# esperto_v1.net
KiCad netlist of a schematic drawn in EAGLE
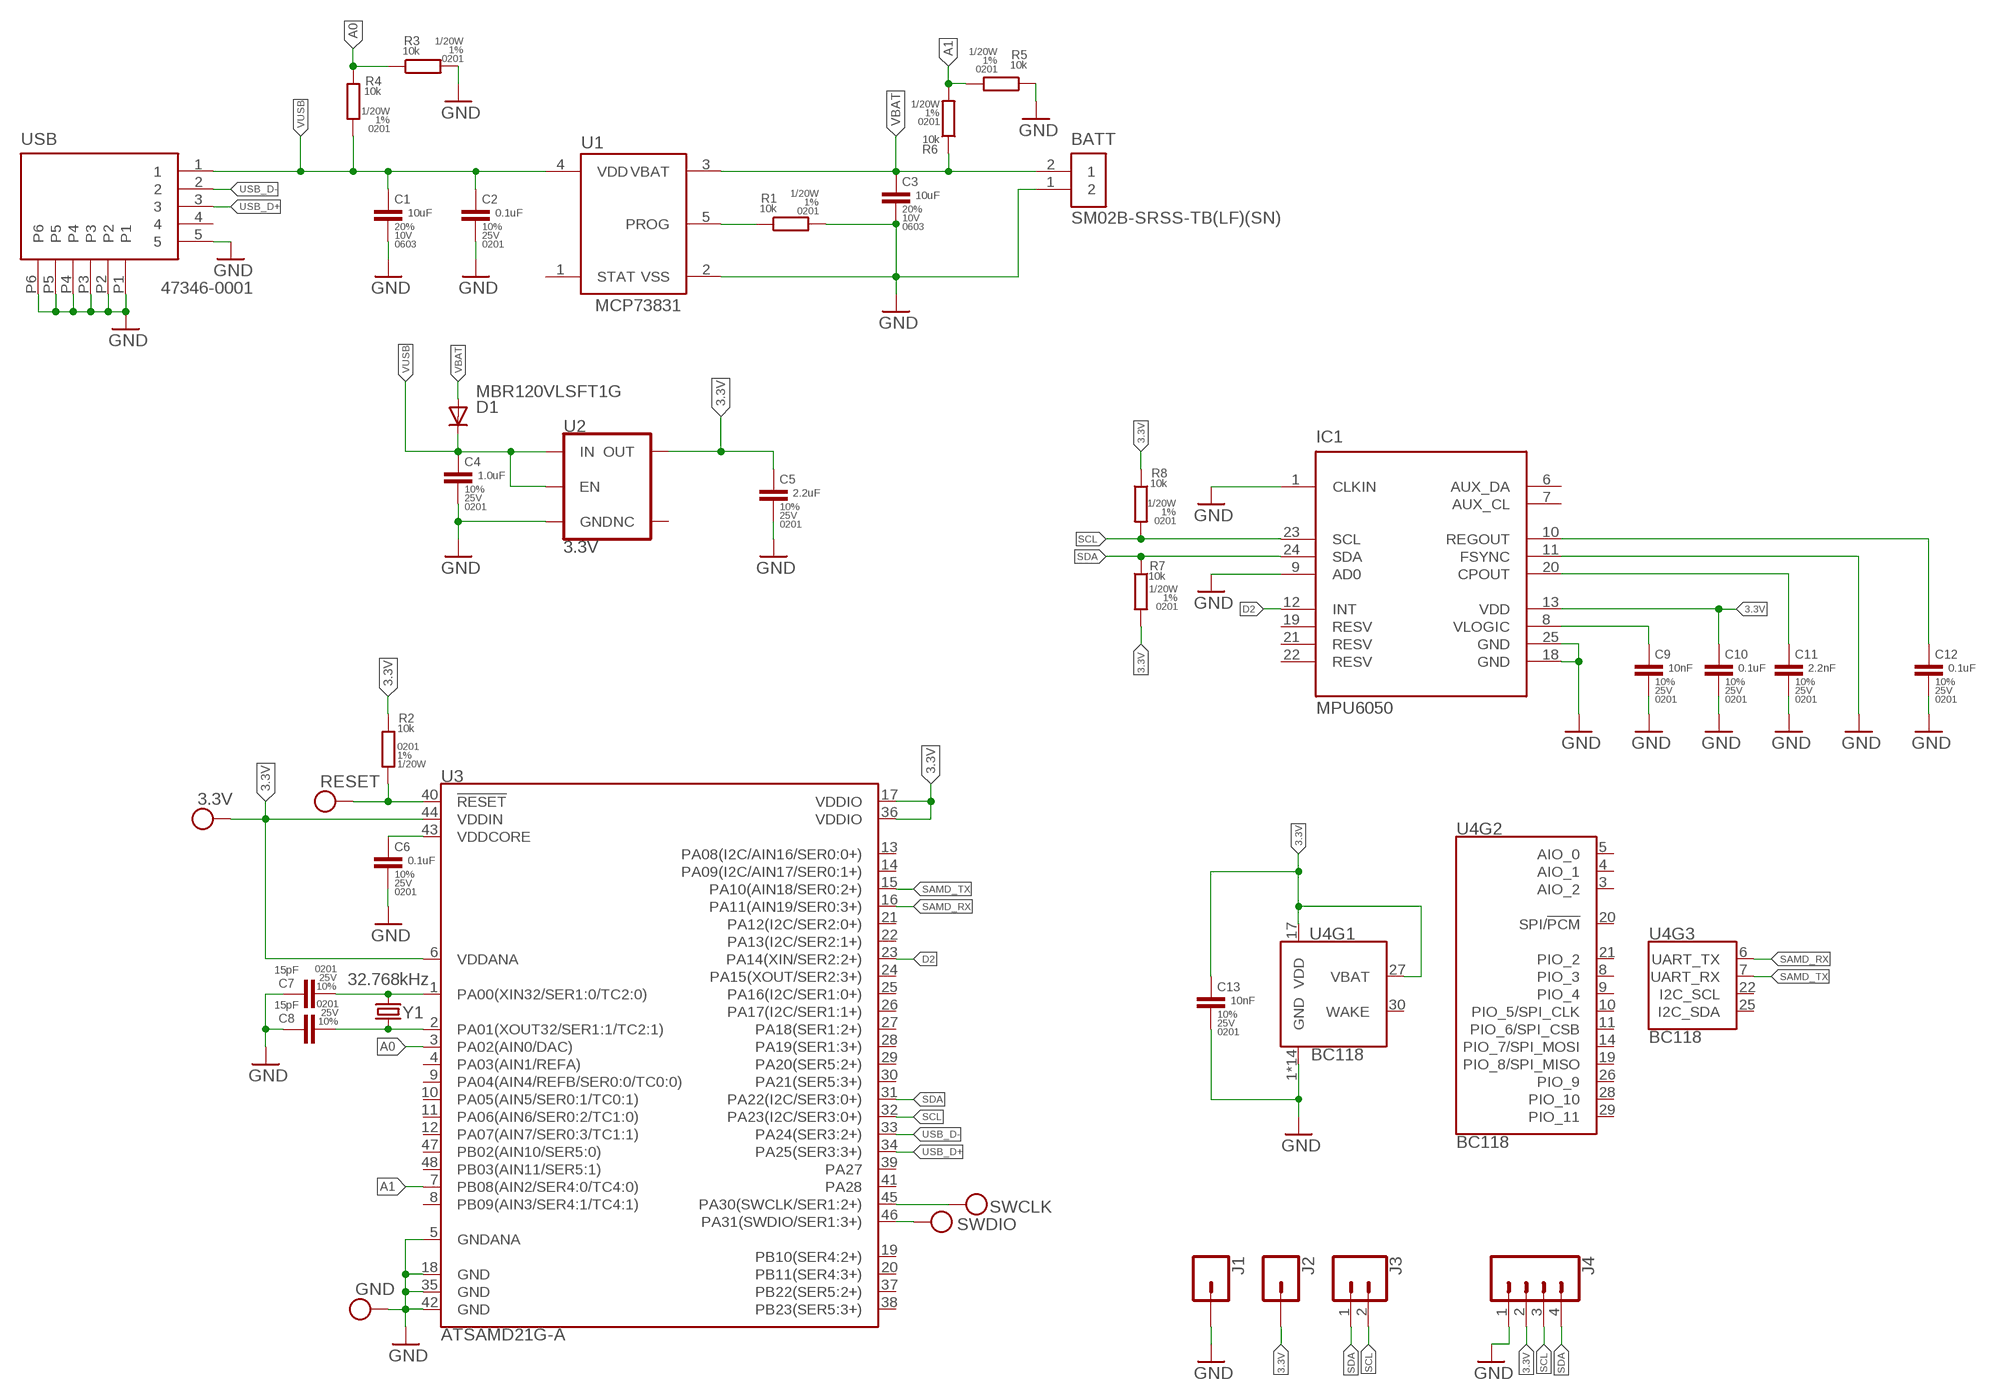
[diagram p0: schematic, sheet 1]

(export (version "E")
  (design (tool "Eeschema 10.0.6"))
  (components
    (comp (ref "3.3V")
      (value "PIN_1X.05\"1")
      (footprint "eagle-import:1X.05_")
      (libsource (lib "eagle-import") (part "PIN_1X.05{dblquote}1"))
    )
    (comp (ref "BATT")
      (value "SM02B-SRSS-TB(LF)(SN)")
      (footprint "eagle-import:JST_SH_2X1")
      (fields (field (name "PARTNO") "AS-ITM-00231"))
      (libsource (lib "eagle-import") (part "AS-ITM-00231"))
    )
    (comp (ref "C1")
      (value "10uF")
      (footprint "eagle-import:C0603_MURATA_GRM18")
      (fields (field (name "TOLERANCE") "20%"))
      (libsource (lib "eagle-import") (part "C-EUC0603_MURATA_GRM18"))
    )
    (comp (ref "C2")
      (value "0.1uF")
      (footprint "eagle-import:C0201_MURATA_GRM03")
      (fields (field (name "TOLERANCE") "10%"))
      (libsource (lib "eagle-import") (part "C-EUC0201_MURATA_GRM03"))
    )
    (comp (ref "C3")
      (value "10uF")
      (footprint "eagle-import:C0603_MURATA_GRM18")
      (fields (field (name "TOLERANCE") "20%"))
      (libsource (lib "eagle-import") (part "C-EUC0603_MURATA_GRM18"))
    )
    (comp (ref "C4")
      (value "1.0uF")
      (footprint "eagle-import:C0201_MURATA_GRM03")
      (fields (field (name "TOLERANCE") "10%"))
      (libsource (lib "eagle-import") (part "C-EUC0201_MURATA_GRM03"))
    )
    (comp (ref "C5")
      (value "2.2uF")
      (footprint "eagle-import:C0201_MURATA_GRM03")
      (fields (field (name "TOLERANCE") "10%"))
      (libsource (lib "eagle-import") (part "C-EUC0201_MURATA_GRM03"))
    )
    (comp (ref "C6")
      (value "0.1uF")
      (footprint "eagle-import:C0201_MURATA_GRM03")
      (fields (field (name "TOLERANCE") "10%"))
      (libsource (lib "eagle-import") (part "C-EUC0201_MURATA_GRM03"))
    )
    (comp (ref "C7")
      (value "15pF")
      (footprint "eagle-import:C0201_MURATA_GRM03")
      (fields (field (name "RATING") "25V") (field (name "TOLERANCE") "10%") (field (name "PACKAGE") "0201"))
      (libsource (lib "eagle-import") (part "C-EUC0201_MURATA_GRM03"))
    )
    (comp (ref "C8")
      (value "15pF")
      (footprint "eagle-import:C0201_MURATA_GRM03")
      (fields (field (name "RATING") "25V") (field (name "TOLERANCE") "10%") (field (name "PACKAGE") "0201"))
      (libsource (lib "eagle-import") (part "C-EUC0201_MURATA_GRM03"))
    )
    (comp (ref "C9")
      (value "10nF")
      (footprint "eagle-import:C0201_MURATA_GRM03")
      (fields (field (name "TOLERANCE") "10%"))
      (libsource (lib "eagle-import") (part "C-EUC0201_MURATA_GRM03"))
    )
    (comp (ref "C10")
      (value "0.1uF")
      (footprint "eagle-import:C0201_MURATA_GRM03")
      (fields (field (name "TOLERANCE") "10%"))
      (libsource (lib "eagle-import") (part "C-EUC0201_MURATA_GRM03"))
    )
    (comp (ref "C11")
      (value "2.2nF")
      (footprint "eagle-import:C0201_MURATA_GRM03")
      (fields (field (name "TOLERANCE") "10%"))
      (libsource (lib "eagle-import") (part "C-EUC0201_MURATA_GRM03"))
    )
    (comp (ref "C12")
      (value "0.1uF")
      (footprint "eagle-import:C0201_MURATA_GRM03")
      (fields (field (name "TOLERANCE") "10%"))
      (libsource (lib "eagle-import") (part "C-EUC0201_MURATA_GRM03"))
    )
    (comp (ref "C13")
      (value "10nF")
      (footprint "eagle-import:C0201_MURATA_GRM03")
      (fields (field (name "TOLERANCE") "10%"))
      (libsource (lib "eagle-import") (part "C-EUC0201_MURATA_GRM03"))
    )
    (comp (ref "D1")
      (value "MBR120VLSFT1G")
      (footprint "eagle-import:SOD-123FL")
      (fields (field (name "PARTNO") "AS-ITM-00111"))
      (libsource (lib "eagle-import") (part "AS-ITM-00111"))
    )
    (comp (ref "GND")
      (value "PIN_1X.05\"1")
      (footprint "eagle-import:1X.05_")
      (libsource (lib "eagle-import") (part "PIN_1X.05{dblquote}1"))
    )
    (comp (ref "IC1")
      (value "MPU6050")
      (footprint "eagle-import:QFN50P400X400X95-25T265X275N")
      (libsource (lib "eagle-import") (part "MPU6050"))
    )
    (comp (ref "J1")
      (value "CONN_01")
      (footprint "eagle-import:1X01")
      (libsource (lib "eagle-import") (part "CONN_01"))
    )
    (comp (ref "J2")
      (value "CONN_01")
      (footprint "eagle-import:1X01")
      (libsource (lib "eagle-import") (part "CONN_01"))
    )
    (comp (ref "J3")
      (value "CONN_02")
      (footprint "eagle-import:1X02")
      (libsource (lib "eagle-import") (part "CONN_02"))
    )
    (comp (ref "J4")
      (value "CONN_04")
      (footprint "eagle-import:1X04")
      (libsource (lib "eagle-import") (part "CONN_04"))
    )
    (comp (ref "R1")
      (value "10k")
      (footprint "eagle-import:R0201_VISHAY_CRCW0201")
      (fields (field (name "TOLERANCE") "1%") (field (name "RATING") "1/20W") (field (name "PACKAGE") "0201"))
      (libsource (lib "eagle-import") (part "R-EU_R0201_VISHAY_CRCW0201"))
    )
    (comp (ref "R2")
      (value "10k")
      (footprint "eagle-import:R0201_VISHAY_CRCW0201")
      (fields (field (name "TOLERANCE") "1%"))
      (libsource (lib "eagle-import") (part "R-EU_R0201_VISHAY_CRCW0201"))
    )
    (comp (ref "R3")
      (value "10k")
      (footprint "eagle-import:R0201_VISHAY_CRCW0201")
      (fields (field (name "TOLERANCE") "1%") (field (name "RATING") "1/20W") (field (name "PACKAGE") "0201"))
      (libsource (lib "eagle-import") (part "R-EU_R0201_VISHAY_CRCW0201"))
    )
    (comp (ref "R4")
      (value "10k")
      (footprint "eagle-import:R0201_VISHAY_CRCW0201")
      (fields (field (name "TOLERANCE") "1%") (field (name "RATING") "1/20W") (field (name "PACKAGE") "0201"))
      (libsource (lib "eagle-import") (part "R-EU_R0201_VISHAY_CRCW0201"))
    )
    (comp (ref "R5")
      (value "10k")
      (footprint "eagle-import:R0201_VISHAY_CRCW0201")
      (fields (field (name "TOLERANCE") "1%") (field (name "RATING") "1/20W") (field (name "PACKAGE") "0201"))
      (libsource (lib "eagle-import") (part "R-EU_R0201_VISHAY_CRCW0201"))
    )
    (comp (ref "R6")
      (value "10k")
      (footprint "eagle-import:R0201_VISHAY_CRCW0201")
      (fields (field (name "TOLERANCE") "1%"))
      (libsource (lib "eagle-import") (part "R-EU_R0201_VISHAY_CRCW0201"))
    )
    (comp (ref "R7")
      (value "10k")
      (footprint "eagle-import:R0201_VISHAY_CRCW0201")
      (fields (field (name "TOLERANCE") "1%") (field (name "RATING") "1/20W") (field (name "PACKAGE") "0201"))
      (libsource (lib "eagle-import") (part "R-EU_R0201_VISHAY_CRCW0201"))
    )
    (comp (ref "R8")
      (value "10k")
      (footprint "eagle-import:R0201_VISHAY_CRCW0201")
      (fields (field (name "TOLERANCE") "1%") (field (name "RATING") "1/20W") (field (name "PACKAGE") "0201"))
      (libsource (lib "eagle-import") (part "R-EU_R0201_VISHAY_CRCW0201"))
    )
    (comp (ref "RESET")
      (value "PIN_1X.05\"1")
      (footprint "eagle-import:1X.05_")
      (libsource (lib "eagle-import") (part "PIN_1X.05{dblquote}1"))
    )
    (comp (ref "SWCLK")
      (value "PIN_1X.05\"1")
      (footprint "eagle-import:1X.05_")
      (libsource (lib "eagle-import") (part "PIN_1X.05{dblquote}1"))
    )
    (comp (ref "SWDIO")
      (value "PIN_1X.05\"1")
      (footprint "eagle-import:1X.05_")
      (libsource (lib "eagle-import") (part "PIN_1X.05{dblquote}1"))
    )
    (comp (ref "U1")
      (value "MCP73831")
      (footprint "eagle-import:SOT-23")
      (fields (field (name "PARTNO") "AS-ITM-00136"))
      (libsource (lib "eagle-import") (part "AS-ITM-00136"))
    )
    (comp (ref "U2")
      (value "3.3V")
      (footprint "eagle-import:SOT23-5")
      (libsource (lib "eagle-import") (part "V_REG_AP2112K-3.3V"))
    )
    (comp (ref "U3")
      (value "ATSAMD21G-A")
      (footprint "eagle-import:TQFP-48")
      (libsource (lib "eagle-import") (part "ATSAMD21G-A"))
    )
    (comp (ref "U4")
      (value "BC118")
      (footprint "eagle-import:BC118")
      (libsource (lib "eagle-import") (part "BC118"))
    )
    (comp (ref "USB")
      (value "47346-0001")
      (footprint "eagle-import:MICRO_USB")
      (fields (field (name "PARTNO") "AS-ITM-00021"))
      (libsource (lib "eagle-import") (part "AS-ITM-00021"))
    )
    (comp (ref "Y1")
      (value "32.768kHz")
      (footprint "eagle-import:CRYSTAL-SMD-3.2X1.5MM")
      (libsource (lib "eagle-import") (part "CRYSTAL-32.768KHZSMD-3.2X1.5"))
    )
  )
  (nets
    (net (code "1") (name "3.3V") (class "Default")
      (node (ref "3.3V") (pin "1") (pinfunction "1_1") (pintype "bidirectional"))
      (node (ref "C10") (pin "1") (pinfunction "1_1") (pintype "passive"))
      (node (ref "C13") (pin "1") (pinfunction "1_1") (pintype "passive"))
      (node (ref "C5") (pin "1") (pinfunction "1_1") (pintype "passive"))
      (node (ref "IC1") (pin "13") (pinfunction "VDD_13") (pintype "power_in"))
      (node (ref "J2") (pin "1") (pinfunction "1_1") (pintype "passive"))
      (node (ref "J4") (pin "2") (pinfunction "2_2") (pintype "passive"))
      (node (ref "R2") (pin "1") (pinfunction "1_1") (pintype "passive"))
      (node (ref "R7") (pin "2") (pinfunction "2_2") (pintype "passive"))
      (node (ref "R8") (pin "1") (pinfunction "1_1") (pintype "passive"))
      (node (ref "U2") (pin "5") (pinfunction "OUT_5") (pintype "passive"))
      (node (ref "U3") (pin "17") (pinfunction "VDDIO_17") (pintype "bidirectional"))
      (node (ref "U3") (pin "36") (pinfunction "VDDIO_36") (pintype "bidirectional"))
      (node (ref "U3") (pin "44") (pinfunction "VDDIN_44") (pintype "bidirectional"))
      (node (ref "U3") (pin "6") (pinfunction "VDDANA_6") (pintype "bidirectional"))
      (node (ref "U4") (pin "17") (pinfunction "VDD_17") (pintype "bidirectional"))
      (node (ref "U4") (pin "27") (pinfunction "VBAT_27") (pintype "bidirectional"))
    )
    (net (code "2") (name "A0") (class "Default")
      (node (ref "R3") (pin "1") (pinfunction "1_1") (pintype "passive"))
      (node (ref "R4") (pin "1") (pinfunction "1_1") (pintype "passive"))
      (node (ref "U3") (pin "3") (pinfunction "PA02(AIN0/DAC)_3") (pintype "bidirectional"))
    )
    (net (code "3") (name "A1") (class "Default")
      (node (ref "R5") (pin "2") (pinfunction "2_2") (pintype "passive"))
      (node (ref "R6") (pin "2") (pinfunction "2_2") (pintype "passive"))
      (node (ref "U3") (pin "7") (pinfunction "PB08(AIN2/SER4:0/TC4:0)_7") (pintype "bidirectional"))
    )
    (net (code "4") (name "D2") (class "Default")
      (node (ref "IC1") (pin "12") (pinfunction "INT_12") (pintype "open_collector"))
      (node (ref "U3") (pin "23") (pinfunction "PA14(XIN/SER2:2+)_23") (pintype "bidirectional"))
    )
    (net (code "5") (name "GND") (class "Default")
      (node (ref "BATT") (pin "1") (pinfunction "2_1") (pintype "bidirectional"))
      (node (ref "C1") (pin "2") (pinfunction "2_2") (pintype "passive"))
      (node (ref "C10") (pin "2") (pinfunction "2_2") (pintype "passive"))
      (node (ref "C11") (pin "2") (pinfunction "2_2") (pintype "passive"))
      (node (ref "C12") (pin "2") (pinfunction "2_2") (pintype "passive"))
      (node (ref "C13") (pin "2") (pinfunction "2_2") (pintype "passive"))
      (node (ref "C2") (pin "2") (pinfunction "2_2") (pintype "passive"))
      (node (ref "C3") (pin "2") (pinfunction "2_2") (pintype "passive"))
      (node (ref "C4") (pin "2") (pinfunction "2_2") (pintype "passive"))
      (node (ref "C5") (pin "2") (pinfunction "2_2") (pintype "passive"))
      (node (ref "C6") (pin "2") (pinfunction "2_2") (pintype "passive"))
      (node (ref "C7") (pin "1") (pinfunction "1_1") (pintype "passive"))
      (node (ref "C8") (pin "1") (pinfunction "1_1") (pintype "passive"))
      (node (ref "C9") (pin "2") (pinfunction "2_2") (pintype "passive"))
      (node (ref "GND") (pin "1") (pinfunction "1_1") (pintype "bidirectional"))
      (node (ref "IC1") (pin "1") (pinfunction "CLKIN_1") (pintype "input"))
      (node (ref "IC1") (pin "11") (pinfunction "FSYNC_11") (pintype "input"))
      (node (ref "IC1") (pin "18") (pinfunction "GND_18") (pintype "power_in"))
      (node (ref "IC1") (pin "25") (pinfunction "GND_25") (pintype "power_in"))
      (node (ref "IC1") (pin "9") (pinfunction "AD0_9") (pintype "input"))
      (node (ref "J1") (pin "1") (pinfunction "1_1") (pintype "passive"))
      (node (ref "J4") (pin "1") (pinfunction "1_1") (pintype "passive"))
      (node (ref "R1") (pin "2") (pinfunction "2_2") (pintype "passive"))
      (node (ref "R3") (pin "2") (pinfunction "2_2") (pintype "passive"))
      (node (ref "R5") (pin "1") (pinfunction "1_1") (pintype "passive"))
      (node (ref "U1") (pin "2") (pinfunction "VSS_2") (pintype "bidirectional"))
      (node (ref "U2") (pin "2") (pinfunction "GND_2") (pintype "input"))
      (node (ref "U3") (pin "18") (pinfunction "GND_18") (pintype "bidirectional"))
      (node (ref "U3") (pin "35") (pinfunction "GND_35") (pintype "bidirectional"))
      (node (ref "U3") (pin "42") (pinfunction "GND_42") (pintype "bidirectional"))
      (node (ref "U3") (pin "5") (pinfunction "GNDANA_5") (pintype "bidirectional"))
      (node (ref "U4") (pin "1") (pinfunction "GND_1") (pintype "bidirectional"))
      (node (ref "U4") (pin "12") (pinfunction "GND_12") (pintype "bidirectional"))
      (node (ref "U4") (pin "13") (pinfunction "GND_13") (pintype "bidirectional"))
      (node (ref "U4") (pin "15") (pinfunction "GND_15") (pintype "bidirectional"))
      (node (ref "U4") (pin "16") (pinfunction "GND_16") (pintype "bidirectional"))
      (node (ref "U4") (pin "18") (pinfunction "GND_18") (pintype "bidirectional"))
      (node (ref "U4") (pin "2") (pinfunction "GND_2") (pintype "bidirectional"))
      (node (ref "U4") (pin "23") (pinfunction "GND_23") (pintype "bidirectional"))
      (node (ref "U4") (pin "24") (pinfunction "GND_24") (pintype "bidirectional"))
      (node (ref "U4") (pin "31") (pinfunction "GND_31") (pintype "bidirectional"))
      (node (ref "U4") (pin "32") (pinfunction "GND_32") (pintype "bidirectional"))
      (node (ref "U4") (pin "33") (pinfunction "GND_33") (pintype "bidirectional"))
      (node (ref "U4") (pin "34") (pinfunction "GND_34") (pintype "bidirectional"))
      (node (ref "U4") (pin "35") (pinfunction "GND_35") (pintype "bidirectional"))
      (node (ref "USB") (pin "5") (pinfunction "5_5") (pintype "bidirectional"))
      (node (ref "USB") (pin "P1") (pinfunction "P1_P1") (pintype "bidirectional"))
      (node (ref "USB") (pin "P2") (pinfunction "P2_P2") (pintype "bidirectional"))
      (node (ref "USB") (pin "P3") (pinfunction "P3_P3") (pintype "bidirectional"))
      (node (ref "USB") (pin "P4") (pinfunction "P4_P4") (pintype "bidirectional"))
      (node (ref "USB") (pin "P5") (pinfunction "P5_P5") (pintype "bidirectional"))
      (node (ref "USB") (pin "P6") (pinfunction "P6_P6") (pintype "bidirectional"))
    )
    (net (code "6") (name "Net-(IC1A-CPOUT)") (class "Default")
      (node (ref "C11") (pin "1") (pinfunction "1_1") (pintype "passive"))
      (node (ref "IC1") (pin "20") (pinfunction "CPOUT_20") (pintype "output"))
    )
    (net (code "7") (name "Net-(IC1A-REGOUT)") (class "Default")
      (node (ref "C12") (pin "1") (pinfunction "1_1") (pintype "passive"))
      (node (ref "IC1") (pin "10") (pinfunction "REGOUT_10") (pintype "output"))
    )
    (net (code "8") (name "Net-(IC1A-VLOGIC)") (class "Default")
      (node (ref "C9") (pin "1") (pinfunction "1_1") (pintype "passive"))
      (node (ref "IC1") (pin "8") (pinfunction "VLOGIC_8") (pintype "power_in"))
    )
    (net (code "9") (name "Net-(U1-PROG)") (class "Default")
      (node (ref "R1") (pin "1") (pinfunction "1_1") (pintype "passive"))
      (node (ref "U1") (pin "5") (pinfunction "PROG_5") (pintype "bidirectional"))
    )
    (net (code "10") (name "Net-(U3-PA00(XIN32{slash}SER1:0{slash}TC2:0))") (class "Default")
      (node (ref "C7") (pin "2") (pinfunction "2_2") (pintype "passive"))
      (node (ref "U3") (pin "1") (pinfunction "PA00(XIN32/SER1:0/TC2:0)_1") (pintype "bidirectional"))
      (node (ref "Y1") (pin "P$1") (pinfunction "1_P$1") (pintype "passive"))
    )
    (net (code "11") (name "Net-(U3-PA01(XOUT32{slash}SER1:1{slash}TC2:1))") (class "Default")
      (node (ref "C8") (pin "2") (pinfunction "2_2") (pintype "passive"))
      (node (ref "U3") (pin "2") (pinfunction "PA01(XOUT32/SER1:1/TC2:1)_2") (pintype "bidirectional"))
      (node (ref "Y1") (pin "P$2") (pinfunction "2_P$2") (pintype "passive"))
    )
    (net (code "12") (name "Net-(U3-PA30(SWCLK{slash}SER1:2+))") (class "Default")
      (node (ref "SWCLK") (pin "1") (pinfunction "1_1") (pintype "bidirectional"))
      (node (ref "U3") (pin "45") (pinfunction "PA30(SWCLK/SER1:2+)_45") (pintype "bidirectional"))
    )
    (net (code "13") (name "Net-(U3-PA31(SWDIO{slash}SER1:3+))") (class "Default")
      (node (ref "SWDIO") (pin "1") (pinfunction "1_1") (pintype "bidirectional"))
      (node (ref "U3") (pin "46") (pinfunction "PA31(SWDIO/SER1:3+)_46") (pintype "bidirectional"))
    )
    (net (code "14") (name "Net-(U3-VDDCORE)") (class "Default")
      (node (ref "C6") (pin "1") (pinfunction "1_1") (pintype "passive"))
      (node (ref "U3") (pin "43") (pinfunction "VDDCORE_43") (pintype "bidirectional"))
    )
    (net (code "15") (name "Net-(U3-~{RESET})") (class "Default")
      (node (ref "R2") (pin "2") (pinfunction "2_2") (pintype "passive"))
      (node (ref "RESET") (pin "1") (pinfunction "1_1") (pintype "bidirectional"))
      (node (ref "U3") (pin "40") (pinfunction "~{RESET}_40") (pintype "bidirectional"))
    )
    (net (code "16") (name "SAMD_RX") (class "Default")
      (node (ref "U3") (pin "16") (pinfunction "PA11(AIN19/SER0:3+)_16") (pintype "bidirectional"))
      (node (ref "U4") (pin "6") (pinfunction "UART_TX_6") (pintype "bidirectional"))
    )
    (net (code "17") (name "SAMD_TX") (class "Default")
      (node (ref "U3") (pin "15") (pinfunction "PA10(AIN18/SER0:2+)_15") (pintype "bidirectional"))
      (node (ref "U4") (pin "7") (pinfunction "UART_RX_7") (pintype "bidirectional"))
    )
    (net (code "18") (name "SCL") (class "Default")
      (node (ref "IC1") (pin "23") (pinfunction "SCL_23") (pintype "input"))
      (node (ref "J3") (pin "2") (pinfunction "2_2") (pintype "passive"))
      (node (ref "J4") (pin "3") (pinfunction "3_3") (pintype "passive"))
      (node (ref "R8") (pin "2") (pinfunction "2_2") (pintype "passive"))
      (node (ref "U3") (pin "32") (pinfunction "PA23(I2C/SER3:0+)_32") (pintype "bidirectional"))
    )
    (net (code "19") (name "SDA") (class "Default")
      (node (ref "IC1") (pin "24") (pinfunction "SDA_24") (pintype "bidirectional"))
      (node (ref "J3") (pin "1") (pinfunction "1_1") (pintype "passive"))
      (node (ref "J4") (pin "4") (pinfunction "4_4") (pintype "passive"))
      (node (ref "R7") (pin "1") (pinfunction "1_1") (pintype "passive"))
      (node (ref "U3") (pin "31") (pinfunction "PA22(I2C/SER3:0+)_31") (pintype "bidirectional"))
    )
    (net (code "20") (name "USB_D+") (class "Default")
      (node (ref "U3") (pin "34") (pinfunction "PA25(SER3:3+)_34") (pintype "bidirectional"))
      (node (ref "USB") (pin "3") (pinfunction "3_3") (pintype "bidirectional"))
    )
    (net (code "21") (name "USB_D-") (class "Default")
      (node (ref "U3") (pin "33") (pinfunction "PA24(SER3:2+)_33") (pintype "bidirectional"))
      (node (ref "USB") (pin "2") (pinfunction "2_2") (pintype "bidirectional"))
    )
    (net (code "22") (name "VBAT") (class "Default")
      (node (ref "BATT") (pin "2") (pinfunction "1_2") (pintype "bidirectional"))
      (node (ref "C3") (pin "1") (pinfunction "1_1") (pintype "passive"))
      (node (ref "D1") (pin "A") (pinfunction "A_A") (pintype "passive"))
      (node (ref "R6") (pin "1") (pinfunction "1_1") (pintype "passive"))
      (node (ref "U1") (pin "3") (pinfunction "VBAT_3") (pintype "bidirectional"))
    )
    (net (code "23") (name "VUSB") (class "Default")
      (node (ref "C1") (pin "1") (pinfunction "1_1") (pintype "passive"))
      (node (ref "C2") (pin "1") (pinfunction "1_1") (pintype "passive"))
      (node (ref "C4") (pin "1") (pinfunction "1_1") (pintype "passive"))
      (node (ref "D1") (pin "C") (pinfunction "C_C") (pintype "passive"))
      (node (ref "R4") (pin "2") (pinfunction "2_2") (pintype "passive"))
      (node (ref "U1") (pin "4") (pinfunction "VDD_4") (pintype "bidirectional"))
      (node (ref "U2") (pin "1") (pinfunction "IN_1") (pintype "input"))
      (node (ref "U2") (pin "3") (pinfunction "EN_3") (pintype "input"))
      (node (ref "USB") (pin "1") (pinfunction "1_1") (pintype "bidirectional"))
    )
    (net (code "24") (name "unconnected-(IC1A-AUX_CL-Pad7)") (class "Default")
      (node (ref "IC1") (pin "7") (pinfunction "AUX_CL_7") (pintype "bidirectional"))
    )
    (net (code "25") (name "unconnected-(IC1A-AUX_DA-Pad6)") (class "Default")
      (node (ref "IC1") (pin "6") (pinfunction "AUX_DA_6") (pintype "bidirectional"))
    )
    (net (code "26") (name "unconnected-(IC1A-RESV-Pad19)") (class "Default")
      (node (ref "IC1") (pin "19") (pinfunction "RESV_19") (pintype "passive"))
    )
    (net (code "27") (name "unconnected-(IC1A-RESV-Pad21)") (class "Default")
      (node (ref "IC1") (pin "21") (pinfunction "RESV_21") (pintype "passive"))
    )
    (net (code "28") (name "unconnected-(IC1A-RESV-Pad22)") (class "Default")
      (node (ref "IC1") (pin "22") (pinfunction "RESV_22") (pintype "passive"))
    )
    (net (code "29") (name "unconnected-(U1-STAT-Pad1)") (class "Default")
      (node (ref "U1") (pin "1") (pinfunction "STAT_1") (pintype "bidirectional"))
    )
    (net (code "30") (name "unconnected-(U2-NC-Pad4)") (class "Default")
      (node (ref "U2") (pin "4") (pinfunction "NC_4") (pintype "no_connect"))
    )
    (net (code "31") (name "unconnected-(U3-PA03(AIN1{slash}REFA)-Pad4)") (class "Default")
      (node (ref "U3") (pin "4") (pinfunction "PA03(AIN1/REFA)_4") (pintype "bidirectional"))
    )
    (net (code "32") (name "unconnected-(U3-PA04(AIN4{slash}REFB{slash}SER0:0{slash}TC0:0)-Pad9)") (class "Default")
      (node (ref "U3") (pin "9") (pinfunction "PA04(AIN4/REFB/SER0:0/TC0:0)_9") (pintype "bidirectional"))
    )
    (net (code "33") (name "unconnected-(U3-PA05(AIN5{slash}SER0:1{slash}TC0:1)-Pad10)") (class "Default")
      (node (ref "U3") (pin "10") (pinfunction "PA05(AIN5/SER0:1/TC0:1)_10") (pintype "bidirectional"))
    )
    (net (code "34") (name "unconnected-(U3-PA06(AIN6{slash}SER0:2{slash}TC1:0)-Pad11)") (class "Default")
      (node (ref "U3") (pin "11") (pinfunction "PA06(AIN6/SER0:2/TC1:0)_11") (pintype "bidirectional"))
    )
    (net (code "35") (name "unconnected-(U3-PA07(AIN7{slash}SER0:3{slash}TC1:1)-Pad12)") (class "Default")
      (node (ref "U3") (pin "12") (pinfunction "PA07(AIN7/SER0:3/TC1:1)_12") (pintype "bidirectional"))
    )
    (net (code "36") (name "unconnected-(U3-PA08(I2C{slash}AIN16{slash}SER0:0+)-Pad13)") (class "Default")
      (node (ref "U3") (pin "13") (pinfunction "PA08(I2C/AIN16/SER0:0+)_13") (pintype "bidirectional"))
    )
    (net (code "37") (name "unconnected-(U3-PA09(I2C{slash}AIN17{slash}SER0:1+)-Pad14)") (class "Default")
      (node (ref "U3") (pin "14") (pinfunction "PA09(I2C/AIN17/SER0:1+)_14") (pintype "bidirectional"))
    )
    (net (code "38") (name "unconnected-(U3-PA12(I2C{slash}SER2:0+)-Pad21)") (class "Default")
      (node (ref "U3") (pin "21") (pinfunction "PA12(I2C/SER2:0+)_21") (pintype "bidirectional"))
    )
    (net (code "39") (name "unconnected-(U3-PA13(I2C{slash}SER2:1+)-Pad22)") (class "Default")
      (node (ref "U3") (pin "22") (pinfunction "PA13(I2C/SER2:1+)_22") (pintype "bidirectional"))
    )
    (net (code "40") (name "unconnected-(U3-PA15(XOUT{slash}SER2:3+)-Pad24)") (class "Default")
      (node (ref "U3") (pin "24") (pinfunction "PA15(XOUT/SER2:3+)_24") (pintype "bidirectional"))
    )
    (net (code "41") (name "unconnected-(U3-PA16(I2C{slash}SER1:0+)-Pad25)") (class "Default")
      (node (ref "U3") (pin "25") (pinfunction "PA16(I2C/SER1:0+)_25") (pintype "bidirectional"))
    )
    (net (code "42") (name "unconnected-(U3-PA17(I2C{slash}SER1:1+)-Pad26)") (class "Default")
      (node (ref "U3") (pin "26") (pinfunction "PA17(I2C/SER1:1+)_26") (pintype "bidirectional"))
    )
    (net (code "43") (name "unconnected-(U3-PA18(SER1:2+)-Pad27)") (class "Default")
      (node (ref "U3") (pin "27") (pinfunction "PA18(SER1:2+)_27") (pintype "bidirectional"))
    )
    (net (code "44") (name "unconnected-(U3-PA19(SER1:3+)-Pad28)") (class "Default")
      (node (ref "U3") (pin "28") (pinfunction "PA19(SER1:3+)_28") (pintype "bidirectional"))
    )
    (net (code "45") (name "unconnected-(U3-PA20(SER5:2+)-Pad29)") (class "Default")
      (node (ref "U3") (pin "29") (pinfunction "PA20(SER5:2+)_29") (pintype "bidirectional"))
    )
    (net (code "46") (name "unconnected-(U3-PA21(SER5:3+)-Pad30)") (class "Default")
      (node (ref "U3") (pin "30") (pinfunction "PA21(SER5:3+)_30") (pintype "bidirectional"))
    )
    (net (code "47") (name "unconnected-(U3-PA27-Pad39)") (class "Default")
      (node (ref "U3") (pin "39") (pinfunction "PA27_39") (pintype "bidirectional"))
    )
    (net (code "48") (name "unconnected-(U3-PA28-Pad41)") (class "Default")
      (node (ref "U3") (pin "41") (pinfunction "PA28_41") (pintype "bidirectional"))
    )
    (net (code "49") (name "unconnected-(U3-PB02(AIN10{slash}SER5:0)-Pad47)") (class "Default")
      (node (ref "U3") (pin "47") (pinfunction "PB02(AIN10/SER5:0)_47") (pintype "bidirectional"))
    )
    (net (code "50") (name "unconnected-(U3-PB03(AIN11{slash}SER5:1)-Pad48)") (class "Default")
      (node (ref "U3") (pin "48") (pinfunction "PB03(AIN11/SER5:1)_48") (pintype "bidirectional"))
    )
    (net (code "51") (name "unconnected-(U3-PB09(AIN3{slash}SER4:1{slash}TC4:1)-Pad8)") (class "Default")
      (node (ref "U3") (pin "8") (pinfunction "PB09(AIN3/SER4:1/TC4:1)_8") (pintype "bidirectional"))
    )
    (net (code "52") (name "unconnected-(U3-PB10(SER4:2+)-Pad19)") (class "Default")
      (node (ref "U3") (pin "19") (pinfunction "PB10(SER4:2+)_19") (pintype "bidirectional"))
    )
    (net (code "53") (name "unconnected-(U3-PB11(SER4:3+)-Pad20)") (class "Default")
      (node (ref "U3") (pin "20") (pinfunction "PB11(SER4:3+)_20") (pintype "bidirectional"))
    )
    (net (code "54") (name "unconnected-(U3-PB22(SER5:2+)-Pad37)") (class "Default")
      (node (ref "U3") (pin "37") (pinfunction "PB22(SER5:2+)_37") (pintype "bidirectional"))
    )
    (net (code "55") (name "unconnected-(U3-PB23(SER5:3+)-Pad38)") (class "Default")
      (node (ref "U3") (pin "38") (pinfunction "PB23(SER5:3+)_38") (pintype "bidirectional"))
    )
    (net (code "56") (name "unconnected-(U4A-WAKE-Pad30)") (class "Default")
      (node (ref "U4") (pin "30") (pinfunction "WAKE_30") (pintype "bidirectional"))
    )
    (net (code "57") (name "unconnected-(U4B-AIO_0-Pad5)") (class "Default")
      (node (ref "U4") (pin "5") (pinfunction "AIO_0_5") (pintype "bidirectional"))
    )
    (net (code "58") (name "unconnected-(U4B-AIO_1-Pad4)") (class "Default")
      (node (ref "U4") (pin "4") (pinfunction "AIO_1_4") (pintype "bidirectional"))
    )
    (net (code "59") (name "unconnected-(U4B-AIO_2-Pad3)") (class "Default")
      (node (ref "U4") (pin "3") (pinfunction "AIO_2_3") (pintype "bidirectional"))
    )
    (net (code "60") (name "unconnected-(U4B-PIO_2-Pad21)") (class "Default")
      (node (ref "U4") (pin "21") (pinfunction "PIO_2_21") (pintype "bidirectional"))
    )
    (net (code "61") (name "unconnected-(U4B-PIO_3-Pad8)") (class "Default")
      (node (ref "U4") (pin "8") (pinfunction "PIO_3_8") (pintype "bidirectional"))
    )
    (net (code "62") (name "unconnected-(U4B-PIO_4-Pad9)") (class "Default")
      (node (ref "U4") (pin "9") (pinfunction "PIO_4_9") (pintype "bidirectional"))
    )
    (net (code "63") (name "unconnected-(U4B-PIO_5{slash}SPI_CLK-Pad10)") (class "Default")
      (node (ref "U4") (pin "10") (pinfunction "PIO_5/SPI_CLK_10") (pintype "bidirectional"))
    )
    (net (code "64") (name "unconnected-(U4B-PIO_6{slash}SPI_CSB-Pad11)") (class "Default")
      (node (ref "U4") (pin "11") (pinfunction "PIO_6/SPI_CSB_11") (pintype "bidirectional"))
    )
    (net (code "65") (name "unconnected-(U4B-PIO_7{slash}SPI_MOSI-Pad14)") (class "Default")
      (node (ref "U4") (pin "14") (pinfunction "PIO_7/SPI_MOSI_14") (pintype "bidirectional"))
    )
    (net (code "66") (name "unconnected-(U4B-PIO_8{slash}SPI_MISO-Pad19)") (class "Default")
      (node (ref "U4") (pin "19") (pinfunction "PIO_8/SPI_MISO_19") (pintype "bidirectional"))
    )
    (net (code "67") (name "unconnected-(U4B-PIO_9-Pad26)") (class "Default")
      (node (ref "U4") (pin "26") (pinfunction "PIO_9_26") (pintype "bidirectional"))
    )
    (net (code "68") (name "unconnected-(U4B-PIO_10-Pad28)") (class "Default")
      (node (ref "U4") (pin "28") (pinfunction "PIO_10_28") (pintype "bidirectional"))
    )
    (net (code "69") (name "unconnected-(U4B-PIO_11-Pad29)") (class "Default")
      (node (ref "U4") (pin "29") (pinfunction "PIO_11_29") (pintype "bidirectional"))
    )
    (net (code "70") (name "unconnected-(U4B-SPI{slash}~{PCM}-Pad20)") (class "Default")
      (node (ref "U4") (pin "20") (pinfunction "SPI/~{PCM}_20") (pintype "bidirectional"))
    )
    (net (code "71") (name "unconnected-(U4C-I2C_SCL-Pad22)") (class "Default")
      (node (ref "U4") (pin "22") (pinfunction "I2C_SCL_22") (pintype "bidirectional"))
    )
    (net (code "72") (name "unconnected-(U4C-I2C_SDA-Pad25)") (class "Default")
      (node (ref "U4") (pin "25") (pinfunction "I2C_SDA_25") (pintype "bidirectional"))
    )
    (net (code "73") (name "unconnected-(USB-Pad4)") (class "Default")
      (node (ref "USB") (pin "4") (pinfunction "4_4") (pintype "bidirectional"))
    )
  )
)
